# low-pass-filter.net
KiCad netlist of a schematic drawn in Altium Designer
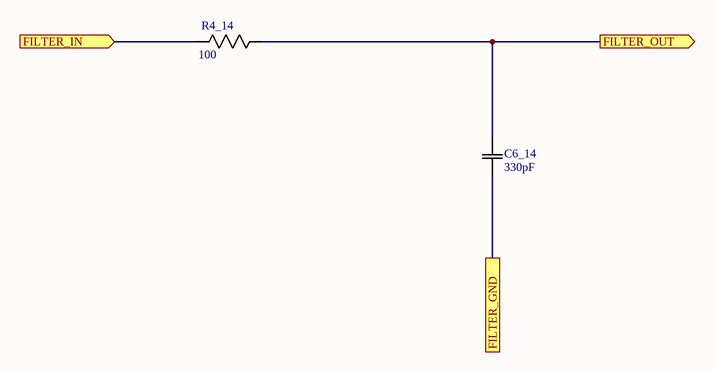
[diagram p0: low-pass-filter.SchDoc]

(export (version "E")
  (design (tool "Eeschema 10.0.6"))
  (components
    (comp (ref "C6_14")
      (value "330pF")
      (footprint "0805")
      (description "CAP CER 330PF 16V X5R 0603/0805")
      (fields (field (name "PART NUMBER") "CAP 330pF 16V") (field (name "TOLERANCE") "10%"))
      (libsource (lib "Capacitor_Library") (part "CAP 330pF 16V"))
    )
    (comp (ref "R4_14")
      (value "100")
      (footprint "0805")
      (description "RES SMD 100 OHM 5% 1/8W 0805")
      (fields (field (name "TOLERANCE") "5%") (field (name "PART NUMBER") "RES 100.0 1/8W 5%"))
      (libsource (lib "Resistor_Library") (part "RES 100.0 1/8W"))
    )
  )
  (nets
    (net (code "1") (name "/FILTER_GND") (class "Default")
      (node (ref "C6_14") (pin "1") (pinfunction "C1_1") (pintype "passive"))
    )
    (net (code "2") (name "/FILTER_IN") (class "Default")
      (node (ref "R4_14") (pin "2") (pinfunction "R2_2") (pintype "passive"))
    )
    (net (code "3") (name "/FILTER_OUT") (class "Default")
      (node (ref "C6_14") (pin "2") (pinfunction "C2_2") (pintype "passive"))
      (node (ref "R4_14") (pin "1") (pinfunction "R1_1") (pintype "passive"))
    )
  )
)
